# Nusbio_Flash_Extension.net
KiCad netlist of a schematic drawn in EAGLE
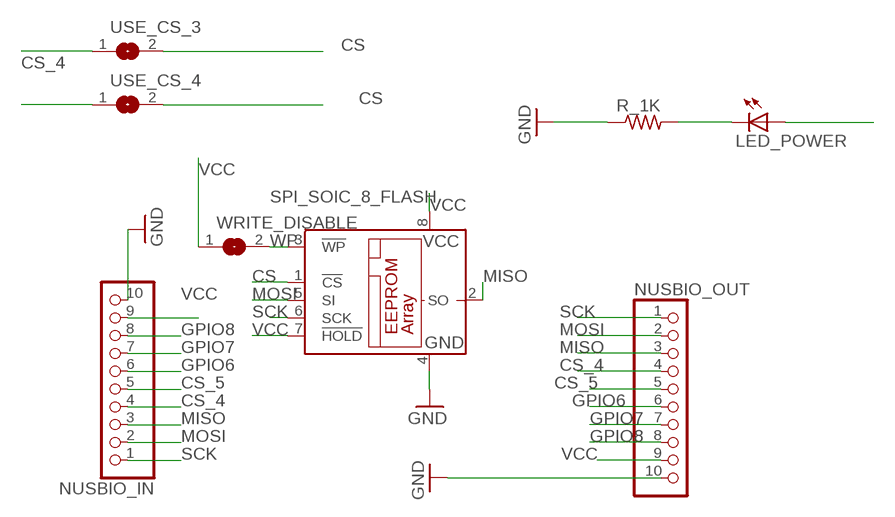
[diagram p0: schematic, sheet 1]

(export (version "E")
  (design (tool "Eeschema 10.0.6"))
  (components
    (comp (ref "LED_POWER")
      (value "LEDSMT1206")
      (footprint "eagle-import:1206")
      (libsource (lib "eagle-import") (part "LEDSMT1206"))
    )
    (comp (ref "NUSBIO_IN")
      (value "PINHD-1X10")
      (footprint "eagle-import:1X10-BIG")
      (libsource (lib "eagle-import") (part "PINHD-1X10"))
    )
    (comp (ref "NUSBIO_OUT")
      (value "PINHD-1X10")
      (footprint "eagle-import:1X10-BIG")
      (libsource (lib "eagle-import") (part "PINHD-1X10"))
    )
    (comp (ref "R_1K")
      (value "R-US_R1206")
      (footprint "eagle-import:R1206")
      (libsource (lib "eagle-import") (part "R-US_R1206"))
    )
    (comp (ref "SPI_SOIC_8_FLASH")
      (value "25AA080SN")
      (footprint "eagle-import:SO-08")
      (fields (field (name "MF") "MICROCHIP") (field (name "MPN") "25AA080/SN"))
      (libsource (lib "eagle-import") (part "25SNAA080"))
    )
    (comp (ref "USE_CS_3")
      (value "SOLDERJUMPERREFLOW")
      (footprint "eagle-import:SOLDERJUMPER_REFLOW")
      (libsource (lib "eagle-import") (part "SOLDERJUMPERREFLOW"))
    )
    (comp (ref "USE_CS_4")
      (value "SOLDERJUMPERREFLOW")
      (footprint "eagle-import:SOLDERJUMPER_REFLOW")
      (libsource (lib "eagle-import") (part "SOLDERJUMPERREFLOW"))
    )
    (comp (ref "WRITE_DISABLE")
      (value "SOLDERJUMPERREFLOW")
      (footprint "eagle-import:SOLDERJUMPER_REFLOW")
      (libsource (lib "eagle-import") (part "SOLDERJUMPERREFLOW"))
    )
  )
  (nets
    (net (code "1") (name "/CS") (class "Default")
      (node (ref "SPI_SOIC_8_FLASH") (pin "1") (pinfunction "~{CS}_1") (pintype "input"))
      (node (ref "USE_CS_3") (pin "2") (pinfunction "2_2") (pintype "passive"))
      (node (ref "USE_CS_4") (pin "2") (pinfunction "2_2") (pintype "passive"))
    )
    (net (code "2") (name "/CS_4") (class "Default")
      (node (ref "NUSBIO_IN") (pin "4") (pinfunction "4_4") (pintype "passive"))
      (node (ref "NUSBIO_OUT") (pin "4") (pinfunction "4_4") (pintype "passive"))
      (node (ref "USE_CS_3") (pin "1") (pinfunction "1_1") (pintype "passive"))
    )
    (net (code "3") (name "/CS_5") (class "Default")
      (node (ref "NUSBIO_IN") (pin "5") (pinfunction "5_5") (pintype "passive"))
      (node (ref "NUSBIO_OUT") (pin "5") (pinfunction "5_5") (pintype "passive"))
      (node (ref "USE_CS_4") (pin "1") (pinfunction "1_1") (pintype "passive"))
    )
    (net (code "4") (name "/GPIO6") (class "Default")
      (node (ref "NUSBIO_IN") (pin "6") (pinfunction "6_6") (pintype "passive"))
      (node (ref "NUSBIO_OUT") (pin "6") (pinfunction "6_6") (pintype "passive"))
    )
    (net (code "5") (name "/GPIO7") (class "Default")
      (node (ref "NUSBIO_IN") (pin "7") (pinfunction "7_7") (pintype "passive"))
      (node (ref "NUSBIO_OUT") (pin "7") (pinfunction "7_7") (pintype "passive"))
    )
    (net (code "6") (name "/GPIO8") (class "Default")
      (node (ref "NUSBIO_IN") (pin "8") (pinfunction "8_8") (pintype "passive"))
      (node (ref "NUSBIO_OUT") (pin "8") (pinfunction "8_8") (pintype "passive"))
    )
    (net (code "7") (name "/MISO") (class "Default")
      (node (ref "NUSBIO_IN") (pin "3") (pinfunction "3_3") (pintype "passive"))
      (node (ref "NUSBIO_OUT") (pin "3") (pinfunction "3_3") (pintype "passive"))
      (node (ref "SPI_SOIC_8_FLASH") (pin "2") (pinfunction "SO_2") (pintype "bidirectional"))
    )
    (net (code "8") (name "/MOSI") (class "Default")
      (node (ref "NUSBIO_IN") (pin "2") (pinfunction "2_2") (pintype "passive"))
      (node (ref "NUSBIO_OUT") (pin "2") (pinfunction "2_2") (pintype "passive"))
      (node (ref "SPI_SOIC_8_FLASH") (pin "5") (pinfunction "SI_5") (pintype "input"))
    )
    (net (code "9") (name "/SCK") (class "Default")
      (node (ref "NUSBIO_IN") (pin "1") (pinfunction "1_1") (pintype "passive"))
      (node (ref "NUSBIO_OUT") (pin "1") (pinfunction "1_1") (pintype "passive"))
      (node (ref "SPI_SOIC_8_FLASH") (pin "6") (pinfunction "SCK_6") (pintype "input"))
    )
    (net (code "10") (name "/VCC") (class "Default")
      (node (ref "LED_POWER") (pin "A") (pinfunction "A_A") (pintype "passive"))
      (node (ref "NUSBIO_IN") (pin "9") (pinfunction "9_9") (pintype "passive"))
      (node (ref "NUSBIO_OUT") (pin "9") (pinfunction "9_9") (pintype "passive"))
      (node (ref "SPI_SOIC_8_FLASH") (pin "7") (pinfunction "~{HOLD}_7") (pintype "input"))
      (node (ref "SPI_SOIC_8_FLASH") (pin "8") (pinfunction "VCC_8") (pintype "power_in"))
      (node (ref "WRITE_DISABLE") (pin "1") (pinfunction "1_1") (pintype "passive"))
    )
    (net (code "11") (name "/WP") (class "Default")
      (node (ref "SPI_SOIC_8_FLASH") (pin "3") (pinfunction "~{WP}_3") (pintype "input"))
      (node (ref "WRITE_DISABLE") (pin "2") (pinfunction "2_2") (pintype "passive"))
    )
    (net (code "12") (name "GND") (class "Default")
      (node (ref "NUSBIO_IN") (pin "10") (pinfunction "10_10") (pintype "passive"))
      (node (ref "NUSBIO_OUT") (pin "10") (pinfunction "10_10") (pintype "passive"))
      (node (ref "R_1K") (pin "1") (pinfunction "1_1") (pintype "passive"))
      (node (ref "SPI_SOIC_8_FLASH") (pin "4") (pinfunction "GND_4") (pintype "power_in"))
    )
    (net (code "13") (name "Net-(LED_POWER-PadC)") (class "Default")
      (node (ref "LED_POWER") (pin "C") (pinfunction "C_C") (pintype "passive"))
      (node (ref "R_1K") (pin "2") (pinfunction "2_2") (pintype "passive"))
    )
  )
)
